# MainBoard_V0_5.net
KiCad netlist of a schematic drawn in EAGLE
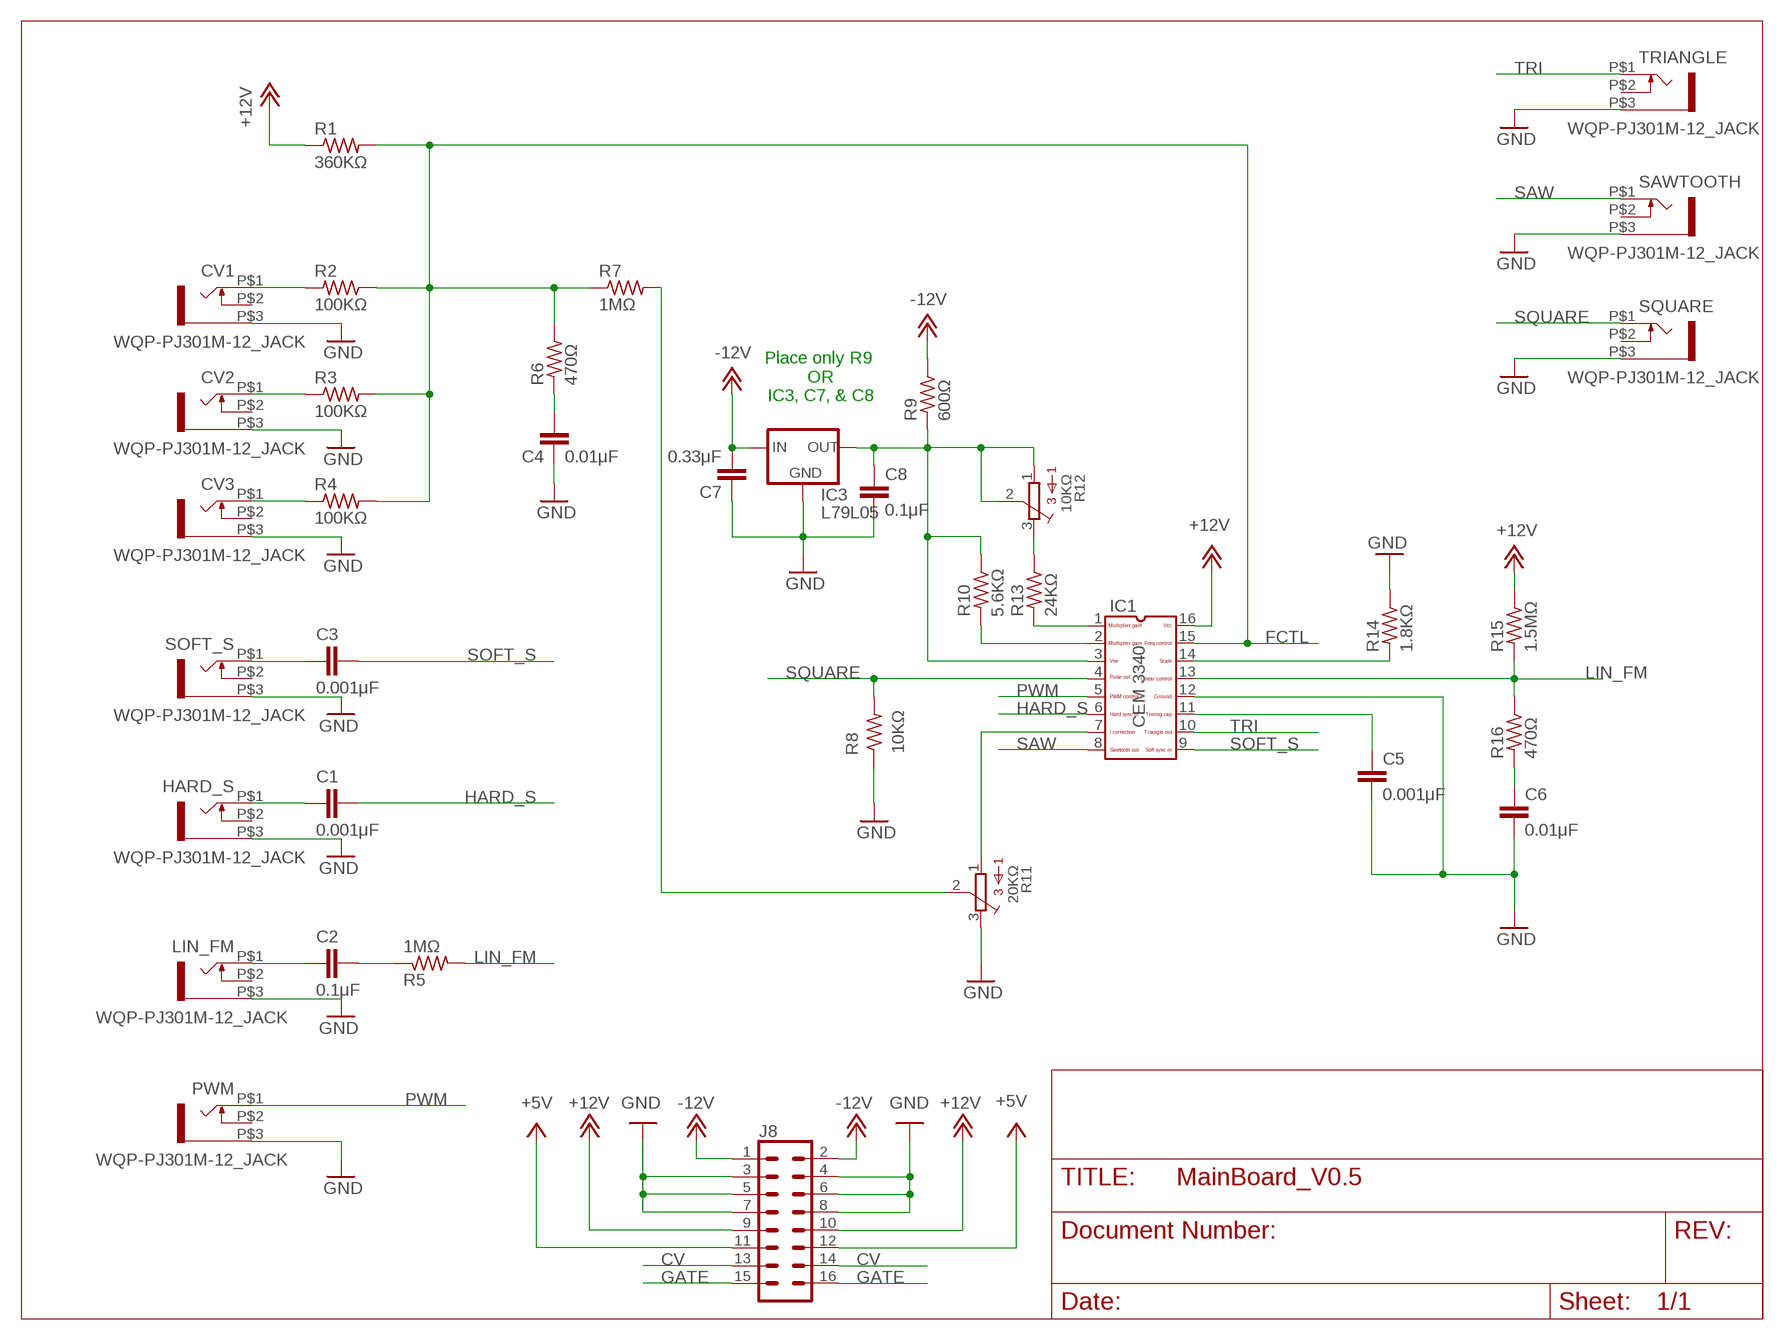
[diagram p0: schematic, sheet 1]

(export (version "E")
  (design (tool "Eeschema 10.0.6"))
  (components
    (comp (ref "C1")
      (value "0.001μF")
      (footprint "eagle-import:C050-025X075")
      (libsource (lib "eagle-import") (part "C-EU050-025X075"))
    )
    (comp (ref "C2")
      (value "0.1μF")
      (footprint "eagle-import:C050-025X075")
      (libsource (lib "eagle-import") (part "C-EU050-025X075"))
    )
    (comp (ref "C3")
      (value "0.001μF")
      (footprint "eagle-import:C050-025X075")
      (libsource (lib "eagle-import") (part "C-EU050-025X075"))
    )
    (comp (ref "C4")
      (value "0.01μF")
      (footprint "eagle-import:C050-025X075")
      (libsource (lib "eagle-import") (part "C-EU050-025X075"))
    )
    (comp (ref "C5")
      (value "0.001μF")
      (footprint "eagle-import:C050-025X075")
      (libsource (lib "eagle-import") (part "C-EU050-025X075"))
    )
    (comp (ref "C6")
      (value "0.01μF")
      (footprint "eagle-import:C050-025X075")
      (libsource (lib "eagle-import") (part "C-EU050-025X075"))
    )
    (comp (ref "C7")
      (value "0.33μF")
      (footprint "eagle-import:C050-025X075")
      (libsource (lib "eagle-import") (part "C-EU050-025X075"))
    )
    (comp (ref "C8")
      (value "0.1μF")
      (footprint "eagle-import:C050-025X075")
      (libsource (lib "eagle-import") (part "C-EU050-025X075"))
    )
    (comp (ref "CV1")
      (value "WQP-PJ301M-12_JACK")
      (footprint "eagle-import:WQP-PJ301M-12_JACK")
      (libsource (lib "eagle-import") (part "WQP-PJ301M-12_JACK"))
    )
    (comp (ref "CV2")
      (value "WQP-PJ301M-12_JACK")
      (footprint "eagle-import:WQP-PJ301M-12_JACK")
      (libsource (lib "eagle-import") (part "WQP-PJ301M-12_JACK"))
    )
    (comp (ref "CV3")
      (value "WQP-PJ301M-12_JACK")
      (footprint "eagle-import:WQP-PJ301M-12_JACK")
      (libsource (lib "eagle-import") (part "WQP-PJ301M-12_JACK"))
    )
    (comp (ref "HARD_S")
      (value "WQP-PJ301M-12_JACK")
      (footprint "eagle-import:WQP-PJ301M-12_JACK")
      (libsource (lib "eagle-import") (part "WQP-PJ301M-12_JACK"))
    )
    (comp (ref "IC1")
      (value "CEM3340")
      (footprint "eagle-import:DIL16")
      (libsource (lib "eagle-import") (part "CEM3340"))
    )
    (comp (ref "IC3")
      (value "L79L05")
      (footprint "eagle-import:TO-92")
      (libsource (lib "eagle-import") (part "V_REG_79LXX"))
    )
    (comp (ref "J8")
      (value "CONN_08X2_SHROUD")
      (footprint "eagle-import:2X8-SHROUDED_LOCK")
      (libsource (lib "eagle-import") (part "CONN_08X2_SHROUD"))
    )
    (comp (ref "LIN_FM")
      (value "WQP-PJ301M-12_JACK")
      (footprint "eagle-import:WQP-PJ301M-12_JACK")
      (libsource (lib "eagle-import") (part "WQP-PJ301M-12_JACK"))
    )
    (comp (ref "PWM")
      (value "WQP-PJ301M-12_JACK")
      (footprint "eagle-import:WQP-PJ301M-12_JACK")
      (libsource (lib "eagle-import") (part "WQP-PJ301M-12_JACK"))
    )
    (comp (ref "R1")
      (value "360KΩ")
      (footprint "eagle-import:0207_10")
      (libsource (lib "eagle-import") (part "R-US_0207/10"))
    )
    (comp (ref "R2")
      (value "100KΩ")
      (footprint "eagle-import:0207_10")
      (libsource (lib "eagle-import") (part "R-US_0207/10"))
    )
    (comp (ref "R3")
      (value "100KΩ")
      (footprint "eagle-import:0207_10")
      (libsource (lib "eagle-import") (part "R-US_0207/10"))
    )
    (comp (ref "R4")
      (value "100KΩ")
      (footprint "eagle-import:0207_10")
      (libsource (lib "eagle-import") (part "R-US_0207/10"))
    )
    (comp (ref "R5")
      (value "1MΩ")
      (footprint "eagle-import:0207_10")
      (libsource (lib "eagle-import") (part "R-US_0207/10"))
    )
    (comp (ref "R6")
      (value "470Ω")
      (footprint "eagle-import:0207_10")
      (libsource (lib "eagle-import") (part "R-US_0207/10"))
    )
    (comp (ref "R7")
      (value "1MΩ")
      (footprint "eagle-import:0207_10")
      (libsource (lib "eagle-import") (part "R-US_0207/10"))
    )
    (comp (ref "R8")
      (value "10KΩ")
      (footprint "eagle-import:0207_10")
      (libsource (lib "eagle-import") (part "R-US_0207/10"))
    )
    (comp (ref "R9")
      (value "600Ω")
      (footprint "eagle-import:0207_10")
      (libsource (lib "eagle-import") (part "R-US_0207/10"))
    )
    (comp (ref "R10")
      (value "5.6KΩ")
      (footprint "eagle-import:0207_10")
      (libsource (lib "eagle-import") (part "R-US_0207/10"))
    )
    (comp (ref "R11")
      (value "20KΩ")
      (footprint "eagle-import:3386W")
      (libsource (lib "eagle-import") (part "3386-W"))
    )
    (comp (ref "R12")
      (value "10KΩ")
      (footprint "eagle-import:3386W")
      (libsource (lib "eagle-import") (part "3386-W"))
    )
    (comp (ref "R13")
      (value "24KΩ")
      (footprint "eagle-import:0207_10")
      (libsource (lib "eagle-import") (part "R-US_0207/10"))
    )
    (comp (ref "R14")
      (value "1.8KΩ")
      (footprint "eagle-import:0207_10")
      (libsource (lib "eagle-import") (part "R-US_0207/10"))
    )
    (comp (ref "R15")
      (value "1.5MΩ")
      (footprint "eagle-import:0207_10")
      (libsource (lib "eagle-import") (part "R-US_0207/10"))
    )
    (comp (ref "R16")
      (value "470Ω")
      (footprint "eagle-import:0207_10")
      (libsource (lib "eagle-import") (part "R-US_0207/10"))
    )
    (comp (ref "SAWTOOTH")
      (value "WQP-PJ301M-12_JACK")
      (footprint "eagle-import:WQP-PJ301M-12_JACK")
      (libsource (lib "eagle-import") (part "WQP-PJ301M-12_JACK"))
    )
    (comp (ref "SOFT_S")
      (value "WQP-PJ301M-12_JACK")
      (footprint "eagle-import:WQP-PJ301M-12_JACK")
      (libsource (lib "eagle-import") (part "WQP-PJ301M-12_JACK"))
    )
    (comp (ref "SQUARE")
      (value "WQP-PJ301M-12_JACK")
      (footprint "eagle-import:WQP-PJ301M-12_JACK")
      (libsource (lib "eagle-import") (part "WQP-PJ301M-12_JACK"))
    )
    (comp (ref "TRIANGLE")
      (value "WQP-PJ301M-12_JACK")
      (footprint "eagle-import:WQP-PJ301M-12_JACK")
      (libsource (lib "eagle-import") (part "WQP-PJ301M-12_JACK"))
    )
  )
  (nets
    (net (code "1") (name "+5V") (class "Default")
      (node (ref "J8") (pin "11") (pinfunction "11_11") (pintype "passive"))
      (node (ref "J8") (pin "12") (pinfunction "12_12") (pintype "passive"))
    )
    (net (code "2") (name "+12V") (class "Default")
      (node (ref "IC1") (pin "16") (pinfunction "16_16") (pintype "power_in"))
      (node (ref "J8") (pin "10") (pinfunction "10_10") (pintype "passive"))
      (node (ref "J8") (pin "9") (pinfunction "9_9") (pintype "passive"))
      (node (ref "R1") (pin "1") (pinfunction "1_1") (pintype "passive"))
      (node (ref "R15") (pin "1") (pinfunction "1_1") (pintype "passive"))
    )
    (net (code "3") (name "-12V") (class "Default")
      (node (ref "C7") (pin "2") (pinfunction "2_2") (pintype "passive"))
      (node (ref "IC3") (pin "2") (pinfunction "IN_2") (pintype "input"))
      (node (ref "J8") (pin "1") (pinfunction "1_1") (pintype "passive"))
      (node (ref "J8") (pin "2") (pinfunction "2_2") (pintype "passive"))
      (node (ref "R9") (pin "1") (pinfunction "1_1") (pintype "passive"))
    )
    (net (code "4") (name "/CV") (class "Default")
      (node (ref "J8") (pin "13") (pinfunction "13_13") (pintype "passive"))
      (node (ref "J8") (pin "14") (pinfunction "14_14") (pintype "passive"))
    )
    (net (code "5") (name "/FCTL") (class "Default")
      (node (ref "IC1") (pin "15") (pinfunction "15_15") (pintype "input"))
      (node (ref "R1") (pin "2") (pinfunction "2_2") (pintype "passive"))
      (node (ref "R2") (pin "1") (pinfunction "1_1") (pintype "passive"))
      (node (ref "R3") (pin "2") (pinfunction "2_2") (pintype "passive"))
      (node (ref "R4") (pin "2") (pinfunction "2_2") (pintype "passive"))
      (node (ref "R6") (pin "1") (pinfunction "1_1") (pintype "passive"))
      (node (ref "R7") (pin "1") (pinfunction "1_1") (pintype "passive"))
    )
    (net (code "6") (name "/GATE") (class "Default")
      (node (ref "J8") (pin "15") (pinfunction "15_15") (pintype "passive"))
      (node (ref "J8") (pin "16") (pinfunction "16_16") (pintype "passive"))
    )
    (net (code "7") (name "/HARD_S") (class "Default")
      (node (ref "C1") (pin "2") (pinfunction "2_2") (pintype "passive"))
      (node (ref "IC1") (pin "6") (pinfunction "6_6") (pintype "input"))
    )
    (net (code "8") (name "/LIN_FM") (class "Default")
      (node (ref "IC1") (pin "13") (pinfunction "13_13") (pintype "input"))
      (node (ref "R15") (pin "2") (pinfunction "2_2") (pintype "passive"))
      (node (ref "R16") (pin "1") (pinfunction "1_1") (pintype "passive"))
      (node (ref "R5") (pin "2") (pinfunction "2_2") (pintype "passive"))
    )
    (net (code "9") (name "/PWM") (class "Default")
      (node (ref "IC1") (pin "5") (pinfunction "5_5") (pintype "input"))
      (node (ref "PWM") (pin "P$1") (pinfunction "2_P$1") (pintype "passive"))
    )
    (net (code "10") (name "/SAW") (class "Default")
      (node (ref "IC1") (pin "8") (pinfunction "8_8") (pintype "output"))
      (node (ref "SAWTOOTH") (pin "P$1") (pinfunction "2_P$1") (pintype "passive"))
    )
    (net (code "11") (name "/SOFT_S") (class "Default")
      (node (ref "C3") (pin "1") (pinfunction "1_1") (pintype "passive"))
      (node (ref "IC1") (pin "9") (pinfunction "9_9") (pintype "input"))
    )
    (net (code "12") (name "/SQUARE") (class "Default")
      (node (ref "IC1") (pin "4") (pinfunction "4_4") (pintype "output"))
      (node (ref "R8") (pin "2") (pinfunction "2_2") (pintype "passive"))
      (node (ref "SQUARE") (pin "P$1") (pinfunction "2_P$1") (pintype "passive"))
    )
    (net (code "13") (name "/TRI") (class "Default")
      (node (ref "IC1") (pin "10") (pinfunction "10_10") (pintype "output"))
      (node (ref "TRIANGLE") (pin "P$1") (pinfunction "2_P$1") (pintype "passive"))
    )
    (net (code "14") (name "GND") (class "Default")
      (node (ref "C4") (pin "2") (pinfunction "2_2") (pintype "passive"))
      (node (ref "C5") (pin "2") (pinfunction "2_2") (pintype "passive"))
      (node (ref "C6") (pin "2") (pinfunction "2_2") (pintype "passive"))
      (node (ref "C7") (pin "1") (pinfunction "1_1") (pintype "passive"))
      (node (ref "C8") (pin "2") (pinfunction "2_2") (pintype "passive"))
      (node (ref "CV1") (pin "P$3") (pinfunction "1_P$3") (pintype "passive"))
      (node (ref "CV2") (pin "P$3") (pinfunction "1_P$3") (pintype "passive"))
      (node (ref "CV3") (pin "P$3") (pinfunction "1_P$3") (pintype "passive"))
      (node (ref "HARD_S") (pin "P$3") (pinfunction "1_P$3") (pintype "passive"))
      (node (ref "IC1") (pin "12") (pinfunction "12_12") (pintype "power_in"))
      (node (ref "IC3") (pin "1") (pinfunction "GND_1") (pintype "input"))
      (node (ref "J8") (pin "3") (pinfunction "3_3") (pintype "passive"))
      (node (ref "J8") (pin "4") (pinfunction "4_4") (pintype "passive"))
      (node (ref "J8") (pin "5") (pinfunction "5_5") (pintype "passive"))
      (node (ref "J8") (pin "6") (pinfunction "6_6") (pintype "passive"))
      (node (ref "J8") (pin "7") (pinfunction "7_7") (pintype "passive"))
      (node (ref "J8") (pin "8") (pinfunction "8_8") (pintype "passive"))
      (node (ref "LIN_FM") (pin "P$3") (pinfunction "1_P$3") (pintype "passive"))
      (node (ref "PWM") (pin "P$3") (pinfunction "1_P$3") (pintype "passive"))
      (node (ref "R11") (pin "3") (pinfunction "3_3") (pintype "passive"))
      (node (ref "R14") (pin "1") (pinfunction "1_1") (pintype "passive"))
      (node (ref "R8") (pin "1") (pinfunction "1_1") (pintype "passive"))
      (node (ref "SAWTOOTH") (pin "P$3") (pinfunction "1_P$3") (pintype "passive"))
      (node (ref "SOFT_S") (pin "P$3") (pinfunction "1_P$3") (pintype "passive"))
      (node (ref "SQUARE") (pin "P$3") (pinfunction "1_P$3") (pintype "passive"))
      (node (ref "TRIANGLE") (pin "P$3") (pinfunction "1_P$3") (pintype "passive"))
    )
    (net (code "15") (name "Net-(C2-Pad2)") (class "Default")
      (node (ref "C2") (pin "2") (pinfunction "2_2") (pintype "passive"))
      (node (ref "R5") (pin "1") (pinfunction "1_1") (pintype "passive"))
    )
    (net (code "16") (name "Net-(C4-Pad1)") (class "Default")
      (node (ref "C4") (pin "1") (pinfunction "1_1") (pintype "passive"))
      (node (ref "R6") (pin "2") (pinfunction "2_2") (pintype "passive"))
    )
    (net (code "17") (name "Net-(C5-Pad1)") (class "Default")
      (node (ref "C5") (pin "1") (pinfunction "1_1") (pintype "passive"))
      (node (ref "IC1") (pin "11") (pinfunction "11_11") (pintype "bidirectional"))
    )
    (net (code "18") (name "Net-(C6-Pad1)") (class "Default")
      (node (ref "C6") (pin "1") (pinfunction "1_1") (pintype "passive"))
      (node (ref "R16") (pin "2") (pinfunction "2_2") (pintype "passive"))
    )
    (net (code "19") (name "Net-(CV1-2)") (class "Default")
      (node (ref "CV1") (pin "P$1") (pinfunction "2_P$1") (pintype "passive"))
      (node (ref "R2") (pin "2") (pinfunction "2_2") (pintype "passive"))
    )
    (net (code "20") (name "Net-(CV2-2)") (class "Default")
      (node (ref "CV2") (pin "P$1") (pinfunction "2_P$1") (pintype "passive"))
      (node (ref "R3") (pin "1") (pinfunction "1_1") (pintype "passive"))
    )
    (net (code "21") (name "Net-(CV3-2)") (class "Default")
      (node (ref "CV3") (pin "P$1") (pinfunction "2_P$1") (pintype "passive"))
      (node (ref "R4") (pin "1") (pinfunction "1_1") (pintype "passive"))
    )
    (net (code "22") (name "Net-(HARD_S-2)") (class "Default")
      (node (ref "C1") (pin "1") (pinfunction "1_1") (pintype "passive"))
      (node (ref "HARD_S") (pin "P$1") (pinfunction "2_P$1") (pintype "passive"))
    )
    (net (code "23") (name "Net-(IC1-Pad1)") (class "Default")
      (node (ref "IC1") (pin "1") (pinfunction "1_1") (pintype "bidirectional"))
      (node (ref "R13") (pin "2") (pinfunction "2_2") (pintype "passive"))
    )
    (net (code "24") (name "Net-(IC1-Pad2)") (class "Default")
      (node (ref "IC1") (pin "2") (pinfunction "2_2") (pintype "bidirectional"))
      (node (ref "R10") (pin "2") (pinfunction "2_2") (pintype "passive"))
    )
    (net (code "25") (name "Net-(IC1-Pad7)") (class "Default")
      (node (ref "IC1") (pin "7") (pinfunction "7_7") (pintype "bidirectional"))
      (node (ref "R11") (pin "1") (pinfunction "1_1") (pintype "passive"))
    )
    (net (code "26") (name "Net-(IC1-Pad14)") (class "Default")
      (node (ref "IC1") (pin "14") (pinfunction "14_14") (pintype "input"))
      (node (ref "R14") (pin "2") (pinfunction "2_2") (pintype "passive"))
    )
    (net (code "27") (name "Net-(IC3-OUT)") (class "Default")
      (node (ref "C8") (pin "1") (pinfunction "1_1") (pintype "passive"))
      (node (ref "IC1") (pin "3") (pinfunction "3_3") (pintype "power_in"))
      (node (ref "IC3") (pin "3") (pinfunction "OUT_3") (pintype "passive"))
      (node (ref "R10") (pin "1") (pinfunction "1_1") (pintype "passive"))
      (node (ref "R12") (pin "1") (pinfunction "1_1") (pintype "passive"))
      (node (ref "R12") (pin "2") (pinfunction "2_2") (pintype "passive"))
      (node (ref "R9") (pin "2") (pinfunction "2_2") (pintype "passive"))
    )
    (net (code "28") (name "Net-(LIN_FM-2)") (class "Default")
      (node (ref "C2") (pin "1") (pinfunction "1_1") (pintype "passive"))
      (node (ref "LIN_FM") (pin "P$1") (pinfunction "2_P$1") (pintype "passive"))
    )
    (net (code "29") (name "Net-(R11-Pad2)") (class "Default")
      (node (ref "R11") (pin "2") (pinfunction "2_2") (pintype "passive"))
      (node (ref "R7") (pin "2") (pinfunction "2_2") (pintype "passive"))
    )
    (net (code "30") (name "Net-(R12-Pad3)") (class "Default")
      (node (ref "R12") (pin "3") (pinfunction "3_3") (pintype "passive"))
      (node (ref "R13") (pin "1") (pinfunction "1_1") (pintype "passive"))
    )
    (net (code "31") (name "Net-(SOFT_S-2)") (class "Default")
      (node (ref "C3") (pin "2") (pinfunction "2_2") (pintype "passive"))
      (node (ref "SOFT_S") (pin "P$1") (pinfunction "2_P$1") (pintype "passive"))
    )
    (net (code "32") (name "unconnected-(CV1-3-PadP$2)") (class "Default")
      (node (ref "CV1") (pin "P$2") (pinfunction "3_P$2") (pintype "passive"))
    )
    (net (code "33") (name "unconnected-(CV2-3-PadP$2)") (class "Default")
      (node (ref "CV2") (pin "P$2") (pinfunction "3_P$2") (pintype "passive"))
    )
    (net (code "34") (name "unconnected-(CV3-3-PadP$2)") (class "Default")
      (node (ref "CV3") (pin "P$2") (pinfunction "3_P$2") (pintype "passive"))
    )
    (net (code "35") (name "unconnected-(HARD_S-3-PadP$2)") (class "Default")
      (node (ref "HARD_S") (pin "P$2") (pinfunction "3_P$2") (pintype "passive"))
    )
    (net (code "36") (name "unconnected-(LIN_FM-3-PadP$2)") (class "Default")
      (node (ref "LIN_FM") (pin "P$2") (pinfunction "3_P$2") (pintype "passive"))
    )
    (net (code "37") (name "unconnected-(PWM-3-PadP$2)") (class "Default")
      (node (ref "PWM") (pin "P$2") (pinfunction "3_P$2") (pintype "passive"))
    )
    (net (code "38") (name "unconnected-(SAWTOOTH-3-PadP$2)") (class "Default")
      (node (ref "SAWTOOTH") (pin "P$2") (pinfunction "3_P$2") (pintype "passive"))
    )
    (net (code "39") (name "unconnected-(SOFT_S-3-PadP$2)") (class "Default")
      (node (ref "SOFT_S") (pin "P$2") (pinfunction "3_P$2") (pintype "passive"))
    )
    (net (code "40") (name "unconnected-(SQUARE-3-PadP$2)") (class "Default")
      (node (ref "SQUARE") (pin "P$2") (pinfunction "3_P$2") (pintype "passive"))
    )
    (net (code "41") (name "unconnected-(TRIANGLE-3-PadP$2)") (class "Default")
      (node (ref "TRIANGLE") (pin "P$2") (pinfunction "3_P$2") (pintype "passive"))
    )
  )
)
